# main.net
KiCad netlist of a schematic drawn in Altium Designer
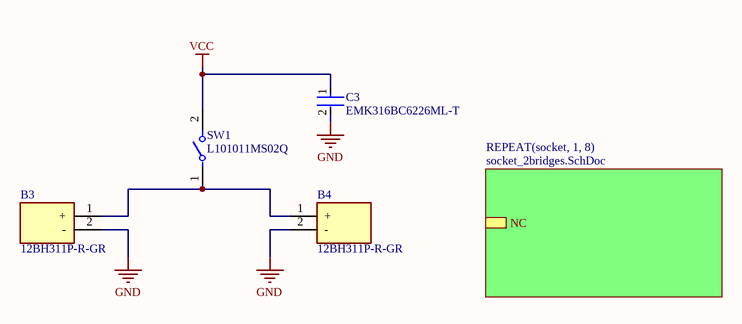
[diagram p0: main.SchDoc]

(export (version "E")
  (design (tool "Eeschema 10.0.6"))
  (components
    (comp (ref "B3")
      (value "12BH311P-R-GR")
      (footprint "12BH311PRGR")
      (description "Cylindrical Battery Contacts, Clips, Holders & Springs 1 \"AA\" PC LDS W/RIB")
      (libsource (lib "") (part "12BH311P-R-GR_1"))
    )
    (comp (ref "B4")
      (value "12BH311P-R-GR")
      (footprint "12BH311PRGR")
      (description "Cylindrical Battery Contacts, Clips, Holders & Springs 1 \"AA\" PC LDS W/RIB")
      (libsource (lib "12BH311P-R-GR") (part "12BH311P-R-GR"))
    )
    (comp (ref "C3")
      (value "EMK316BC6226ML-T")
      (footprint "FP-1206-L_3_2_0_3-W_1_6_0-IPC_A")
      (description "None")
      (fields (field (name "TOLERANCE") "20%"))
      (libsource (lib "Altium Content Vault") (part "11868f565c42a9108669ba33697ecf6"))
    )
    (comp (ref "SW1")
      (value "L101011MS02Q")
      (footprint "FP-L101011MS02Q-MFG")
      (description "SWITCH SLIDE SPST 4A 125V")
      (libsource (lib "Altium Content Vault") (part "bb27bde45df87f1f469753f287ef5ae"))
    )
  )
  (nets
    (net (code "2") (name "GND") (class "Default")
      (node (ref "B3") (pin "2") (pinfunction "-_2") (pintype "passive"))
      (node (ref "B4") (pin "2") (pinfunction "-_2") (pintype "passive"))
      (node (ref "C3") (pin "2") (pinfunction "2_2") (pintype "passive"))
    )
    (net (code "3") (name "Net-(B3-+)") (class "Default")
      (node (ref "B3") (pin "1") (pinfunction "+_1") (pintype "passive"))
      (node (ref "B4") (pin "1") (pinfunction "+_1") (pintype "passive"))
      (node (ref "SW1") (pin "1") (pinfunction "1_1") (pintype "passive"))
    )
    (net (code "4") (name "VCC") (class "Default")
      (node (ref "C3") (pin "1") (pinfunction "1_1") (pintype "passive"))
      (node (ref "SW1") (pin "2") (pinfunction "2_2") (pintype "passive"))
    )
  )
)
